# Sheet1.net
KiCad netlist of a schematic drawn in Altium Designer
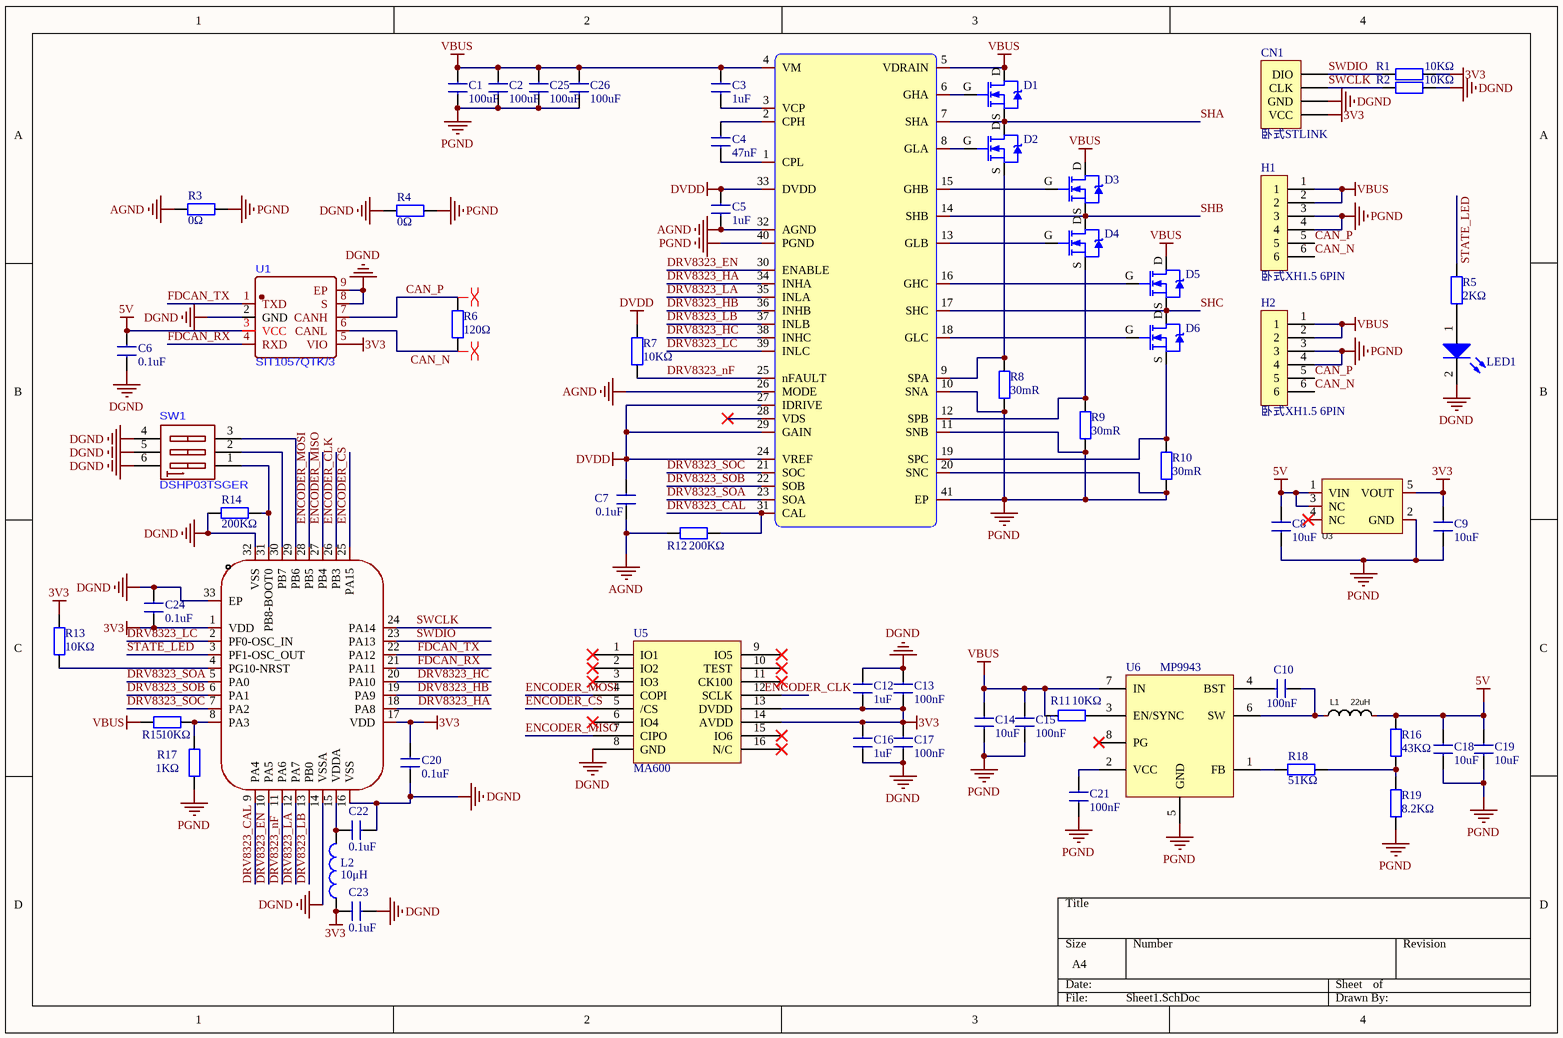
[diagram p0: Sheet1.SchDoc]

(export (version "E")
  (design (tool "Eeschema 10.0.6"))
  (components
    (comp (ref "C1")
      (value "100uF")
      (footprint "1206")
      (description "1210贴片电容")
      (libsource (lib "Integrated_Library1") (part "1210贴片电容"))
    )
    (comp (ref "C2")
      (value "100uF")
      (footprint "1206")
      (description "1210贴片电容")
      (libsource (lib "Integrated_Library1") (part "1210贴片电容"))
    )
    (comp (ref "C3")
      (value "1uF")
      (footprint "c0402")
      (description "贴片电容0402")
      (libsource (lib "Integrated_Library1") (part "0402贴片电容"))
    )
    (comp (ref "C4")
      (value "47nF")
      (footprint "c0402")
      (description "贴片电容0402")
      (libsource (lib "Integrated_Library1") (part "0402贴片电容"))
    )
    (comp (ref "C5")
      (value "1uF")
      (footprint "c0402")
      (description "贴片电容0402")
      (libsource (lib "Integrated_Library1") (part "0402贴片电容"))
    )
    (comp (ref "C6")
      (value "0.1uF")
      (footprint "c0402")
      (description "贴片电容0402")
      (libsource (lib "Integrated_Library1") (part "0402贴片电容"))
    )
    (comp (ref "C7")
      (value "0.1uF")
      (footprint "c0402")
      (description "贴片电容0402")
      (libsource (lib "Integrated_Library1") (part "0402贴片电容"))
    )
    (comp (ref "C8")
      (value "10uF")
      (footprint "c0402")
      (description "贴片电容0402")
      (libsource (lib "Integrated_Library1") (part "0402贴片电容"))
    )
    (comp (ref "C9")
      (value "10uF")
      (footprint "c0402")
      (description "贴片电容0402")
      (libsource (lib "Integrated_Library1") (part "0402贴片电容"))
    )
    (comp (ref "C10")
      (value "100nF")
      (footprint "c0402")
      (description "贴片电容0402")
      (libsource (lib "Integrated_Library1") (part "0402贴片电容"))
    )
    (comp (ref "C12")
      (value "1uF")
      (footprint "C0402")
      (description "贴片电容0402")
      (libsource (lib "Integrated_Library1") (part "0402贴片电容"))
    )
    (comp (ref "C13")
      (value "100nF")
      (footprint "C0402")
      (description "贴片电容0402")
      (libsource (lib "Integrated_Library1") (part "0402贴片电容"))
    )
    (comp (ref "C14")
      (value "10uF")
      (footprint "C0603")
      (description "1210贴片电容")
      (libsource (lib "Integrated_Library1") (part "1210贴片电容"))
    )
    (comp (ref "C15")
      (value "100nF")
      (footprint "c0402")
      (description "贴片电容0402")
      (libsource (lib "Integrated_Library1") (part "0402贴片电容"))
    )
    (comp (ref "C16")
      (value "1uF")
      (footprint "C0402")
      (description "贴片电容0402")
      (libsource (lib "Integrated_Library1") (part "0402贴片电容"))
    )
    (comp (ref "C17")
      (value "100nF")
      (footprint "C0402")
      (description "贴片电容0402")
      (libsource (lib "Integrated_Library1") (part "0402贴片电容"))
    )
    (comp (ref "C18")
      (value "10uF")
      (footprint "C0603")
      (description "1210贴片电容")
      (libsource (lib "Integrated_Library1") (part "1210贴片电容"))
    )
    (comp (ref "C19")
      (value "10uF")
      (footprint "C0603")
      (description "1210贴片电容")
      (libsource (lib "Integrated_Library1") (part "1210贴片电容"))
    )
    (comp (ref "C20")
      (value "0.1uF")
      (footprint "c0402")
      (description "贴片电容0402")
      (libsource (lib "Integrated_Library1") (part "0402贴片电容"))
    )
    (comp (ref "C21")
      (value "100nF")
      (footprint "c0402")
      (description "贴片电容0402")
      (libsource (lib "Integrated_Library1") (part "0402贴片电容"))
    )
    (comp (ref "C22")
      (value "0.1uF")
      (footprint "c0402")
      (description "贴片电容0402")
      (libsource (lib "Integrated_Library1") (part "0402贴片电容"))
    )
    (comp (ref "C23")
      (value "0.1uF")
      (footprint "c0402")
      (description "贴片电容0402")
      (libsource (lib "Integrated_Library1") (part "0402贴片电容"))
    )
    (comp (ref "C24")
      (value "0.1uF")
      (footprint "c0402")
      (description "贴片电容0402")
      (libsource (lib "Integrated_Library1") (part "0402贴片电容"))
    )
    (comp (ref "C25")
      (value "100uF")
      (footprint "1206")
      (description "1210贴片电容")
      (libsource (lib "Integrated_Library1") (part "1210贴片电容"))
    )
    (comp (ref "C26")
      (value "100uF")
      (footprint "1206")
      (description "1210贴片电容")
      (libsource (lib "Integrated_Library1") (part "1210贴片电容"))
    )
    (comp (ref "CN1")
      (value "卧式STLINK")
      (footprint "CONN-SMD_4P-P1.25_GH1.25-4P")
      (libsource (lib "Integrated_Library1") (part "卧式STLINK"))
    )
    (comp (ref "D1")
      (value "NTMFS5C410NL")
      (footprint "DFN-8_L3.0-W3.0-P0.65-BL")
      (description "N沟道MOS管")
      (fields (field (name "PUBLISHER") "Altium Limited"))
      (libsource (lib "En") (part "NTMFS5C410NL"))
    )
    (comp (ref "D2")
      (value "NTMFS5C410NL")
      (footprint "DFN-8_L3.0-W3.0-P0.65-BL")
      (description "N沟道MOS管")
      (fields (field (name "PUBLISHER") "Altium Limited"))
      (libsource (lib "En") (part "NTMFS5C410NL"))
    )
    (comp (ref "D3")
      (value "NTMFS5C410NL")
      (footprint "DFN-8_L3.0-W3.0-P0.65-BL")
      (description "N沟道MOS管")
      (fields (field (name "PUBLISHER") "Altium Limited"))
      (libsource (lib "En") (part "NTMFS5C410NL"))
    )
    (comp (ref "D4")
      (value "NTMFS5C410NL")
      (footprint "DFN-8_L3.0-W3.0-P0.65-BL")
      (description "N沟道MOS管")
      (fields (field (name "PUBLISHER") "Altium Limited"))
      (libsource (lib "En") (part "NTMFS5C410NL"))
    )
    (comp (ref "D5")
      (value "NTMFS5C410NL")
      (footprint "DFN-8_L3.0-W3.0-P0.65-BL")
      (description "N沟道MOS管")
      (fields (field (name "PUBLISHER") "Altium Limited"))
      (libsource (lib "En") (part "NTMFS5C410NL"))
    )
    (comp (ref "D6")
      (value "NTMFS5C410NL")
      (footprint "DFN-8_L3.0-W3.0-P0.65-BL")
      (description "N沟道MOS管")
      (fields (field (name "PUBLISHER") "Altium Limited"))
      (libsource (lib "En") (part "NTMFS5C410NL"))
    )
    (comp (ref "H1")
      (value "卧式XH1.5 6PIN")
      (footprint "CONN-SMD_6P-P1.50_ZX-ZH1.5-6PWT")
      (libsource (lib "En") (part "卧式XH1.5 6PIN"))
    )
    (comp (ref "H2")
      (value "卧式XH1.5 6PIN")
      (footprint "CONN-SMD_6P-P1.50_ZX-ZH1.5-6PWT")
      (libsource (lib "En") (part "卧式XH1.5 6PIN"))
    )
    (comp (ref "L1")
      (value "22uH")
      (footprint "IND-SMD_L2.5-W2.0")
      (description "一体成型屏蔽电感，0530封装，额定电流3A")
      (fields (field (name "MANUFACTURER") "XR(祥如)") (field (name "MANUFACTURER PART") "XR0530-100M"))
      (libsource (lib "Integrated_Library1") (part "0530屏蔽电感"))
    )
    (comp (ref "L2")
      (value "10μH")
      (footprint "L0805")
      (description "0805贴片电感")
      (libsource (lib "Integrated_Library1") (part "0805贴片电感"))
    )
    (comp (ref "LED1")
      (value "LED")
      (footprint "led0805")
      (description "0805贴片LED")
      (libsource (lib "Integrated_Library1") (part "0805贴片LED"))
    )
    (comp (ref "R1")
      (value "10KΩ")
      (footprint "R0402")
      (description "0402贴片电阻")
      (libsource (lib "") (part "0402贴片电阻_3"))
    )
    (comp (ref "R2")
      (value "10KΩ")
      (footprint "R0402")
      (description "0402贴片电阻")
      (libsource (lib "") (part "0402贴片电阻_3"))
    )
    (comp (ref "R3")
      (value "0Ω")
      (footprint "R0402")
      (description "0402贴片电阻")
      (libsource (lib "") (part "0402贴片电阻_3"))
    )
    (comp (ref "R4")
      (value "0Ω")
      (footprint "R0402")
      (description "0402贴片电阻")
      (libsource (lib "") (part "0402贴片电阻_3"))
    )
    (comp (ref "R5")
      (value "2KΩ")
      (footprint "R0402")
      (description "0402贴片电阻")
      (libsource (lib "") (part "0402贴片电阻_1"))
    )
    (comp (ref "R6")
      (value "120Ω")
      (footprint "R0402")
      (description "0402贴片电阻")
      (libsource (lib "") (part "0402贴片电阻_2"))
    )
    (comp (ref "R7")
      (value "10KΩ")
      (footprint "R0402")
      (description "0402贴片电阻")
      (libsource (lib "") (part "0402贴片电阻_1"))
    )
    (comp (ref "R8")
      (value "30mR")
      (footprint "1206")
      (description "2512检流电阻")
      (libsource (lib "Integrated_Library1") (part "2512检流电阻"))
    )
    (comp (ref "R9")
      (value "30mR")
      (footprint "1206")
      (description "2512检流电阻")
      (libsource (lib "Integrated_Library1") (part "2512检流电阻"))
    )
    (comp (ref "R10")
      (value "30mR")
      (footprint "1206")
      (description "2512检流电阻")
      (libsource (lib "Integrated_Library1") (part "2512检流电阻"))
    )
    (comp (ref "R11")
      (value "10KΩ")
      (footprint "R0402")
      (description "0402贴片电阻")
      (libsource (lib "") (part "0402贴片电阻_5"))
    )
    (comp (ref "R12")
      (value "200KΩ")
      (footprint "R0402")
      (description "0402贴片电阻")
      (libsource (lib "Integrated_Library1") (part "0402贴片电阻"))
    )
    (comp (ref "R13")
      (value "10KΩ")
      (footprint "R0402")
      (description "0402贴片电阻")
      (libsource (lib "") (part "0402贴片电阻_1"))
    )
    (comp (ref "R14")
      (value "200KΩ")
      (footprint "R0402")
      (description "0402贴片电阻")
      (libsource (lib "") (part "0402贴片电阻_3"))
    )
    (comp (ref "R15")
      (value "10KΩ")
      (footprint "R0402")
      (description "0402贴片电阻")
      (libsource (lib "Integrated_Library1") (part "0402贴片电阻"))
    )
    (comp (ref "R16")
      (value "43KΩ")
      (footprint "R0402")
      (description "0402贴片电阻")
      (libsource (lib "") (part "0402贴片电阻_4"))
    )
    (comp (ref "R17")
      (value "1KΩ")
      (footprint "R0402")
      (description "0402贴片电阻")
      (libsource (lib "") (part "0402贴片电阻_1"))
    )
    (comp (ref "R18")
      (value "51KΩ")
      (footprint "R0402")
      (description "0402贴片电阻")
      (libsource (lib "") (part "0402贴片电阻_5"))
    )
    (comp (ref "R19")
      (value "8.2KΩ")
      (footprint "R0402")
      (description "0402贴片电阻")
      (libsource (lib "") (part "0402贴片电阻_4"))
    )
    (comp (ref "SW1")
      (value "DSHP03TSGER")
      (footprint "SW-SMD_6P-L5.4-W5.4-P1.27-LS8.4")
      (libsource (lib "Integrated_Library1") (part "DSHP03TSGER"))
    )
    (comp (ref "U1")
      (value "SIT1057QTK/3")
      (footprint "DFN-8_L3.0-W3.0-P0.65-BL-EP")
      (libsource (lib "En") (part "SIT1057QTK/3"))
    )
    (comp (ref "U2")
      (value "DRV8323HRTAR")
      (footprint "QFN-40_L6.0-W6.0-P0.50-BL-EP4.5")
      (fields (field (name "MANUFACTURER") "TI(德州仪器)"))
      (libsource (lib "Integrated_Library1") (part "DRV8323HRTAR"))
    )
    (comp (ref "U3")
      (value "XC6201P332MR-HXY")
      (footprint "SOT-23-5_L3.0-W1.7-P0.95-LS2.8-BR")
      (description "3.3V LDO")
      (fields (field (name "MANUFACTURER") "HXY MOSFET(华轩阳电子)"))
      (libsource (lib "Integrated_Library1") (part "XC6201P332MR-HXY"))
    )
    (comp (ref "U4")
      (value "STM32G431KBU3")
      (footprint "UFQFPN-32_L5.0-W5.0-P0.50-BL-EP3.5")
      (fields (field (name "MANUFACTURER") "ST(意法半导体)"))
      (libsource (lib "Integrated_Library1") (part "STM32G431KBU3"))
    )
    (comp (ref "U5")
      (value "MA600")
      (footprint "qfn-16-l3.0-w3.0-p0.50-tl-ep1.7")
      (description "磁编码器")
      (libsource (lib "Integrated_Library1") (part "MA600"))
    )
    (comp (ref "U6")
      (value "MP9943")
      (footprint "QFN-8 3x3")
      (libsource (lib "Integrated_Library1") (part "MP9943"))
    )
  )
  (nets
    (net (code "2") (name "/CAN_N") (class "Default")
      (node (ref "H1") (pin "6") (pinfunction "6_6") (pintype "passive"))
      (node (ref "H2") (pin "6") (pinfunction "6_6") (pintype "passive"))
      (node (ref "R6") (pin "1") (pinfunction "1_1") (pintype "passive"))
      (node (ref "U1") (pin "6") (pinfunction "CANL_6") (pintype "passive"))
    )
    (net (code "3") (name "/CAN_P") (class "Default")
      (node (ref "H1") (pin "5") (pinfunction "5_5") (pintype "passive"))
      (node (ref "H2") (pin "5") (pinfunction "5_5") (pintype "passive"))
      (node (ref "R6") (pin "2") (pinfunction "2_2") (pintype "passive"))
      (node (ref "U1") (pin "7") (pinfunction "CANH_7") (pintype "passive"))
    )
    (net (code "4") (name "/DRV8323_CAL") (class "Default")
      (node (ref "R12") (pin "1") (pinfunction "1_1") (pintype "passive"))
      (node (ref "U2") (pin "31") (pinfunction "CAL_31") (pintype "passive"))
      (node (ref "U4") (pin "9") (pinfunction "PA4_9") (pintype "passive"))
    )
    (net (code "5") (name "/DRV8323_EN") (class "Default")
      (node (ref "U2") (pin "30") (pinfunction "ENABLE_30") (pintype "passive"))
      (node (ref "U4") (pin "10") (pinfunction "PA5_10") (pintype "passive"))
    )
    (net (code "6") (name "/DRV8323_HA") (class "Default")
      (node (ref "U2") (pin "34") (pinfunction "INHA_34") (pintype "passive"))
      (node (ref "U4") (pin "18") (pinfunction "PA8_18") (pintype "passive"))
    )
    (net (code "7") (name "/DRV8323_HB") (class "Default")
      (node (ref "U2") (pin "36") (pinfunction "INHB_36") (pintype "passive"))
      (node (ref "U4") (pin "19") (pinfunction "PA9_19") (pintype "passive"))
    )
    (net (code "8") (name "/DRV8323_HC") (class "Default")
      (node (ref "U2") (pin "38") (pinfunction "INHC_38") (pintype "passive"))
      (node (ref "U4") (pin "20") (pinfunction "PA10_20") (pintype "passive"))
    )
    (net (code "9") (name "/DRV8323_LA") (class "Default")
      (node (ref "U2") (pin "35") (pinfunction "INLA_35") (pintype "passive"))
      (node (ref "U4") (pin "12") (pinfunction "PA7_12") (pintype "passive"))
    )
    (net (code "10") (name "/DRV8323_LB") (class "Default")
      (node (ref "U2") (pin "37") (pinfunction "INLB_37") (pintype "passive"))
      (node (ref "U4") (pin "13") (pinfunction "PB0_13") (pintype "passive"))
    )
    (net (code "11") (name "/DRV8323_LC") (class "Default")
      (node (ref "U2") (pin "39") (pinfunction "INLC_39") (pintype "passive"))
      (node (ref "U4") (pin "2") (pinfunction "PF0-OSC_IN_2") (pintype "passive"))
    )
    (net (code "12") (name "/DRV8323_SOA") (class "Default")
      (node (ref "U2") (pin "23") (pinfunction "SOA_23") (pintype "passive"))
      (node (ref "U4") (pin "5") (pinfunction "PA0_5") (pintype "passive"))
    )
    (net (code "13") (name "/DRV8323_SOB") (class "Default")
      (node (ref "U2") (pin "22") (pinfunction "SOB_22") (pintype "passive"))
      (node (ref "U4") (pin "6") (pinfunction "PA1_6") (pintype "passive"))
    )
    (net (code "14") (name "/DRV8323_SOC") (class "Default")
      (node (ref "U2") (pin "21") (pinfunction "SOC_21") (pintype "passive"))
      (node (ref "U4") (pin "7") (pinfunction "PA2_7") (pintype "passive"))
    )
    (net (code "15") (name "/DRV8323_nF") (class "Default")
      (node (ref "R7") (pin "2") (pinfunction "2_2") (pintype "passive"))
      (node (ref "U2") (pin "25") (pinfunction "nFAULT_25") (pintype "passive"))
      (node (ref "U4") (pin "11") (pinfunction "PA6_11") (pintype "passive"))
    )
    (net (code "16") (name "/ENCODER_CLK") (class "Default")
      (node (ref "U4") (pin "26") (pinfunction "PB3_26") (pintype "passive"))
      (node (ref "U5") (pin "12") (pinfunction "SCLK_12") (pintype "passive"))
    )
    (net (code "17") (name "/ENCODER_CS") (class "Default")
      (node (ref "U4") (pin "25") (pinfunction "PA15_25") (pintype "passive"))
      (node (ref "U5") (pin "5") (pinfunction "/CS_5") (pintype "passive"))
    )
    (net (code "18") (name "/ENCODER_MISO") (class "Default")
      (node (ref "U4") (pin "27") (pinfunction "PB4_27") (pintype "passive"))
      (node (ref "U5") (pin "7") (pinfunction "CIPO_7") (pintype "passive"))
    )
    (net (code "19") (name "/ENCODER_MOSI") (class "Default")
      (node (ref "U4") (pin "28") (pinfunction "PB5_28") (pintype "passive"))
      (node (ref "U5") (pin "4") (pinfunction "COPI_4") (pintype "passive"))
    )
    (net (code "20") (name "/FDCAN_RX") (class "Default")
      (node (ref "U1") (pin "4") (pinfunction "RXD_4") (pintype "passive"))
      (node (ref "U4") (pin "21") (pinfunction "PA11_21") (pintype "passive"))
    )
    (net (code "21") (name "/FDCAN_TX") (class "Default")
      (node (ref "U1") (pin "1") (pinfunction "TXD_1") (pintype "passive"))
      (node (ref "U4") (pin "22") (pinfunction "PA12_22") (pintype "passive"))
    )
    (net (code "22") (name "/SHA") (class "Default")
      (node (ref "D1") (pin "S") (pinfunction "S_S") (pintype "passive"))
      (node (ref "D2") (pin "D") (pinfunction "D_D") (pintype "passive"))
      (node (ref "U2") (pin "7") (pinfunction "SHA_7") (pintype "passive"))
    )
    (net (code "23") (name "/SHB") (class "Default")
      (node (ref "D3") (pin "S") (pinfunction "S_S") (pintype "passive"))
      (node (ref "D4") (pin "D") (pinfunction "D_D") (pintype "passive"))
      (node (ref "U2") (pin "14") (pinfunction "SHB_14") (pintype "passive"))
    )
    (net (code "24") (name "/SHC") (class "Default")
      (node (ref "D5") (pin "S") (pinfunction "S_S") (pintype "passive"))
      (node (ref "D6") (pin "D") (pinfunction "D_D") (pintype "passive"))
      (node (ref "U2") (pin "17") (pinfunction "SHC_17") (pintype "passive"))
    )
    (net (code "25") (name "/STATE_LED") (class "Default")
      (node (ref "R5") (pin "1") (pinfunction "1_1") (pintype "passive"))
      (node (ref "U4") (pin "3") (pinfunction "PF1-OSC_OUT_3") (pintype "passive"))
    )
    (net (code "26") (name "/SWCLK") (class "Default")
      (node (ref "CN1") (pin "3") (pinfunction "CLK_3") (pintype "passive"))
      (node (ref "R2") (pin "1") (pinfunction "1_1") (pintype "passive"))
      (node (ref "U4") (pin "24") (pinfunction "PA14_24") (pintype "passive"))
    )
    (net (code "27") (name "/SWDIO") (class "Default")
      (node (ref "CN1") (pin "4") (pinfunction "DIO_4") (pintype "passive"))
      (node (ref "R1") (pin "1") (pinfunction "1_1") (pintype "passive"))
      (node (ref "U4") (pin "23") (pinfunction "PA13_23") (pintype "passive"))
    )
    (net (code "28") (name "3V3") (class "Default")
      (node (ref "C12") (pin "1") (pinfunction "1_1") (pintype "passive"))
      (node (ref "C13") (pin "1") (pinfunction "1_1") (pintype "passive"))
      (node (ref "C16") (pin "2") (pinfunction "2_2") (pintype "passive"))
      (node (ref "C17") (pin "2") (pinfunction "2_2") (pintype "passive"))
      (node (ref "C20") (pin "1") (pinfunction "1_1") (pintype "passive"))
      (node (ref "C23") (pin "2") (pinfunction "2_2") (pintype "passive"))
      (node (ref "C24") (pin "1") (pinfunction "1_1") (pintype "passive"))
      (node (ref "C9") (pin "2") (pinfunction "2_2") (pintype "passive"))
      (node (ref "CN1") (pin "1") (pinfunction "VCC_1") (pintype "passive"))
      (node (ref "L2") (pin "1") (pinfunction "1_1") (pintype "passive"))
      (node (ref "R1") (pin "2") (pinfunction "2_2") (pintype "passive"))
      (node (ref "R13") (pin "1") (pinfunction "1_1") (pintype "passive"))
      (node (ref "U1") (pin "5") (pinfunction "VIO_5") (pintype "passive"))
      (node (ref "U3") (pin "5") (pinfunction "VOUT_5") (pintype "passive"))
      (node (ref "U4") (pin "1") (pinfunction "VDD_1") (pintype "passive"))
      (node (ref "U4") (pin "17") (pinfunction "VDD_17") (pintype "passive"))
      (node (ref "U5") (pin "13") (pinfunction "DVDD_13") (pintype "passive"))
      (node (ref "U5") (pin "14") (pinfunction "AVDD_14") (pintype "passive"))
    )
    (net (code "29") (name "5V") (class "Default")
      (node (ref "C18") (pin "2") (pinfunction "2_2") (pintype "passive"))
      (node (ref "C19") (pin "2") (pinfunction "2_2") (pintype "passive"))
      (node (ref "C6") (pin "2") (pinfunction "2_2") (pintype "passive"))
      (node (ref "C8") (pin "2") (pinfunction "2_2") (pintype "passive"))
      (node (ref "L1") (pin "2") (pinfunction "2_2") (pintype "passive"))
      (node (ref "R16") (pin "2") (pinfunction "2_2") (pintype "passive"))
      (node (ref "U1") (pin "3") (pinfunction "VCC_3") (pintype "passive"))
      (node (ref "U3") (pin "1") (pinfunction "VIN_1") (pintype "passive"))
      (node (ref "U3") (pin "3") (pinfunction "NC_3") (pintype "passive"))
    )
    (net (code "30") (name "AGND") (class "Default")
      (node (ref "C5") (pin "1") (pinfunction "1_1") (pintype "passive"))
      (node (ref "C7") (pin "1") (pinfunction "1_1") (pintype "passive"))
      (node (ref "R12") (pin "2") (pinfunction "2_2") (pintype "passive"))
      (node (ref "R3") (pin "1") (pinfunction "1_1") (pintype "passive"))
      (node (ref "U2") (pin "26") (pinfunction "MODE_26") (pintype "passive"))
      (node (ref "U2") (pin "32") (pinfunction "AGND_32") (pintype "passive"))
    )
    (net (code "31") (name "DGND") (class "Default")
      (node (ref "C12") (pin "2") (pinfunction "2_2") (pintype "passive"))
      (node (ref "C13") (pin "2") (pinfunction "2_2") (pintype "passive"))
      (node (ref "C16") (pin "1") (pinfunction "1_1") (pintype "passive"))
      (node (ref "C17") (pin "1") (pinfunction "1_1") (pintype "passive"))
      (node (ref "C20") (pin "2") (pinfunction "2_2") (pintype "passive"))
      (node (ref "C22") (pin "1") (pinfunction "1_1") (pintype "passive"))
      (node (ref "C23") (pin "1") (pinfunction "1_1") (pintype "passive"))
      (node (ref "C24") (pin "2") (pinfunction "2_2") (pintype "passive"))
      (node (ref "C6") (pin "1") (pinfunction "1_1") (pintype "passive"))
      (node (ref "CN1") (pin "2") (pinfunction "GND_2") (pintype "passive"))
      (node (ref "LED1") (pin "2") (pinfunction "K_2") (pintype "passive"))
      (node (ref "R14") (pin "1") (pinfunction "1_1") (pintype "passive"))
      (node (ref "R2") (pin "2") (pinfunction "2_2") (pintype "passive"))
      (node (ref "R4") (pin "1") (pinfunction "1_1") (pintype "passive"))
      (node (ref "SW1") (pin "4") (pinfunction "B3_4") (pintype "passive"))
      (node (ref "SW1") (pin "5") (pinfunction "B2_5") (pintype "passive"))
      (node (ref "SW1") (pin "6") (pinfunction "B1_6") (pintype "passive"))
      (node (ref "U1") (pin "2") (pinfunction "GND_2") (pintype "passive"))
      (node (ref "U1") (pin "8") (pinfunction "S_8") (pintype "passive"))
      (node (ref "U1") (pin "9") (pinfunction "EP_9") (pintype "passive"))
      (node (ref "U4") (pin "14") (pinfunction "VSSA_14") (pintype "passive"))
      (node (ref "U4") (pin "16") (pinfunction "VSS_16") (pintype "passive"))
      (node (ref "U4") (pin "32") (pinfunction "VSS_32") (pintype "passive"))
      (node (ref "U4") (pin "33") (pinfunction "EP_33") (pintype "passive"))
      (node (ref "U5") (pin "8") (pinfunction "GND_8") (pintype "passive"))
    )
    (net (code "32") (name "DVDD") (class "Default")
      (node (ref "C5") (pin "2") (pinfunction "2_2") (pintype "passive"))
      (node (ref "C7") (pin "2") (pinfunction "2_2") (pintype "passive"))
      (node (ref "R7") (pin "1") (pinfunction "1_1") (pintype "passive"))
      (node (ref "U2") (pin "24") (pinfunction "VREF_24") (pintype "passive"))
      (node (ref "U2") (pin "27") (pinfunction "IDRIVE_27") (pintype "passive"))
      (node (ref "U2") (pin "29") (pinfunction "GAIN_29") (pintype "passive"))
      (node (ref "U2") (pin "33") (pinfunction "DVDD_33") (pintype "passive"))
    )
    (net (code "33") (name "Net-(LED1-A)") (class "Default")
      (node (ref "LED1") (pin "1") (pinfunction "A_1") (pintype "passive"))
      (node (ref "R5") (pin "2") (pinfunction "2_2") (pintype "passive"))
    )
    (net (code "34") (name "Net-(R16-Pad1)") (class "Default")
      (node (ref "R16") (pin "1") (pinfunction "1_1") (pintype "passive"))
      (node (ref "R18") (pin "2") (pinfunction "2_2") (pintype "passive"))
      (node (ref "R19") (pin "2") (pinfunction "2_2") (pintype "passive"))
    )
    (net (code "35") (name "Net-(SW1-A1)") (class "Default")
      (node (ref "R14") (pin "2") (pinfunction "2_2") (pintype "passive"))
      (node (ref "SW1") (pin "1") (pinfunction "A1_1") (pintype "passive"))
      (node (ref "U4") (pin "31") (pinfunction "PB8-BOOT0_31") (pintype "passive"))
    )
    (net (code "36") (name "Net-(SW1-A2)") (class "Default")
      (node (ref "SW1") (pin "2") (pinfunction "A2_2") (pintype "passive"))
      (node (ref "U4") (pin "30") (pinfunction "PB7_30") (pintype "passive"))
    )
    (net (code "37") (name "Net-(SW1-A3)") (class "Default")
      (node (ref "SW1") (pin "3") (pinfunction "A3_3") (pintype "passive"))
      (node (ref "U4") (pin "29") (pinfunction "PB6_29") (pintype "passive"))
    )
    (net (code "38") (name "Net-(U2-CPH)") (class "Default")
      (node (ref "C4") (pin "2") (pinfunction "2_2") (pintype "passive"))
      (node (ref "U2") (pin "2") (pinfunction "CPH_2") (pintype "passive"))
    )
    (net (code "39") (name "Net-(U2-CPL)") (class "Default")
      (node (ref "C4") (pin "1") (pinfunction "1_1") (pintype "passive"))
      (node (ref "U2") (pin "1") (pinfunction "CPL_1") (pintype "passive"))
    )
    (net (code "40") (name "Net-(U2-GHA)") (class "Default")
      (node (ref "D1") (pin "G") (pinfunction "G_G") (pintype "passive"))
      (node (ref "U2") (pin "6") (pinfunction "GHA_6") (pintype "passive"))
    )
    (net (code "41") (name "Net-(U2-GHB)") (class "Default")
      (node (ref "D3") (pin "G") (pinfunction "G_G") (pintype "passive"))
      (node (ref "U2") (pin "15") (pinfunction "GHB_15") (pintype "passive"))
    )
    (net (code "42") (name "Net-(U2-GHC)") (class "Default")
      (node (ref "D5") (pin "G") (pinfunction "G_G") (pintype "passive"))
      (node (ref "U2") (pin "16") (pinfunction "GHC_16") (pintype "passive"))
    )
    (net (code "43") (name "Net-(U2-GLA)") (class "Default")
      (node (ref "D2") (pin "G") (pinfunction "G_G") (pintype "passive"))
      (node (ref "U2") (pin "8") (pinfunction "GLA_8") (pintype "passive"))
    )
    (net (code "44") (name "Net-(U2-GLB)") (class "Default")
      (node (ref "D4") (pin "G") (pinfunction "G_G") (pintype "passive"))
      (node (ref "U2") (pin "13") (pinfunction "GLB_13") (pintype "passive"))
    )
    (net (code "45") (name "Net-(U2-GLC)") (class "Default")
      (node (ref "D6") (pin "G") (pinfunction "G_G") (pintype "passive"))
      (node (ref "U2") (pin "18") (pinfunction "GLC_18") (pintype "passive"))
    )
    (net (code "46") (name "Net-(U2-SPA)") (class "Default")
      (node (ref "D2") (pin "S") (pinfunction "S_S") (pintype "passive"))
      (node (ref "R8") (pin "2") (pinfunction "2_2") (pintype "passive"))
      (node (ref "U2") (pin "9") (pinfunction "SPA_9") (pintype "passive"))
    )
    (net (code "47") (name "Net-(U2-SPB)") (class "Default")
      (node (ref "D4") (pin "S") (pinfunction "S_S") (pintype "passive"))
      (node (ref "R9") (pin "2") (pinfunction "2_2") (pintype "passive"))
      (node (ref "U2") (pin "12") (pinfunction "SPB_12") (pintype "passive"))
    )
    (net (code "48") (name "Net-(U2-SPC)") (class "Default")
      (node (ref "D6") (pin "S") (pinfunction "S_S") (pintype "passive"))
      (node (ref "R10") (pin "2") (pinfunction "2_2") (pintype "passive"))
      (node (ref "U2") (pin "19") (pinfunction "SPC_19") (pintype "passive"))
    )
    (net (code "49") (name "Net-(U2-VCP)") (class "Default")
      (node (ref "C3") (pin "1") (pinfunction "1_1") (pintype "passive"))
      (node (ref "U2") (pin "3") (pinfunction "VCP_3") (pintype "passive"))
    )
    (net (code "50") (name "Net-(U4-PA3)") (class "Default")
      (node (ref "R15") (pin "1") (pinfunction "1_1") (pintype "passive"))
      (node (ref "R17") (pin "1") (pinfunction "1_1") (pintype "passive"))
      (node (ref "U4") (pin "8") (pinfunction "PA3_8") (pintype "passive"))
    )
    (net (code "51") (name "Net-(U4-PG10-NRST)") (class "Default")
      (node (ref "R13") (pin "2") (pinfunction "2_2") (pintype "passive"))
      (node (ref "U4") (pin "4") (pinfunction "PG10-NRST_4") (pintype "passive"))
    )
    (net (code "52") (name "Net-(U4-VDDA)") (class "Default")
      (node (ref "C22") (pin "2") (pinfunction "2_2") (pintype "passive"))
      (node (ref "L2") (pin "2") (pinfunction "2_2") (pintype "passive"))
      (node (ref "U4") (pin "15") (pinfunction "VDDA_15") (pintype "passive"))
    )
    (net (code "53") (name "Net-(U6-BST)") (class "Default")
      (node (ref "C10") (pin "1") (pinfunction "1_1") (pintype "passive"))
      (node (ref "U6") (pin "4") (pinfunction "BST_4") (pintype "passive"))
    )
    (net (code "54") (name "Net-(U6-EN{slash}SYNC)") (class "Default")
      (node (ref "R11") (pin "2") (pinfunction "2_2") (pintype "passive"))
      (node (ref "U6") (pin "3") (pinfunction "EN/SYNC_3") (pintype "passive"))
    )
    (net (code "55") (name "Net-(U6-FB)") (class "Default")
      (node (ref "R18") (pin "1") (pinfunction "1_1") (pintype "passive"))
      (node (ref "U6") (pin "1") (pinfunction "FB_1") (pintype "passive"))
    )
    (net (code "56") (name "Net-(U6-SW)") (class "Default")
      (node (ref "C10") (pin "2") (pinfunction "2_2") (pintype "passive"))
      (node (ref "L1") (pin "1") (pinfunction "1_1") (pintype "passive"))
      (node (ref "U6") (pin "6") (pinfunction "SW_6") (pintype "passive"))
    )
    (net (code "57") (name "Net-(U6-VCC)") (class "Default")
      (node (ref "C21") (pin "2") (pinfunction "2_2") (pintype "passive"))
      (node (ref "U6") (pin "2") (pinfunction "VCC_2") (pintype "passive"))
    )
    (net (code "58") (name "PGND") (class "Default")
      (node (ref "C1") (pin "1") (pinfunction "1_1") (pintype "passive"))
      (node (ref "C14") (pin "1") (pinfunction "1_1") (pintype "passive"))
      (node (ref "C15") (pin "1") (pinfunction "1_1") (pintype "passive"))
      (node (ref "C18") (pin "1") (pinfunction "1_1") (pintype "passive"))
      (node (ref "C19") (pin "1") (pinfunction "1_1") (pintype "passive"))
      (node (ref "C2") (pin "1") (pinfunction "1_1") (pintype "passive"))
      (node (ref "C21") (pin "1") (pinfunction "1_1") (pintype "passive"))
      (node (ref "C25") (pin "1") (pinfunction "1_1") (pintype "passive"))
      (node (ref "C26") (pin "1") (pinfunction "1_1") (pintype "passive"))
      (node (ref "C8") (pin "1") (pinfunction "1_1") (pintype "passive"))
      (node (ref "C9") (pin "1") (pinfunction "1_1") (pintype "passive"))
      (node (ref "H1") (pin "3") (pinfunction "3_3") (pintype "passive"))
      (node (ref "H1") (pin "4") (pinfunction "4_4") (pintype "passive"))
      (node (ref "H2") (pin "3") (pinfunction "3_3") (pintype "passive"))
      (node (ref "H2") (pin "4") (pinfunction "4_4") (pintype "passive"))
      (node (ref "R10") (pin "1") (pinfunction "1_1") (pintype "passive"))
      (node (ref "R17") (pin "2") (pinfunction "2_2") (pintype "passive"))
      (node (ref "R19") (pin "1") (pinfunction "1_1") (pintype "passive"))
      (node (ref "R3") (pin "2") (pinfunction "2_2") (pintype "passive"))
      (node (ref "R4") (pin "2") (pinfunction "2_2") (pintype "passive"))
      (node (ref "R8") (pin "1") (pinfunction "1_1") (pintype "passive"))
      (node (ref "R9") (pin "1") (pinfunction "1_1") (pintype "passive"))
      (node (ref "U2") (pin "10") (pinfunction "SNA_10") (pintype "passive"))
      (node (ref "U2") (pin "11") (pinfunction "SNB_11") (pintype "passive"))
      (node (ref "U2") (pin "20") (pinfunction "SNC_20") (pintype "passive"))
      (node (ref "U2") (pin "40") (pinfunction "PGND_40") (pintype "passive"))
      (node (ref "U2") (pin "41") (pinfunction "EP_41") (pintype "passive"))
      (node (ref "U3") (pin "2") (pinfunction "GND_2") (pintype "passive"))
      (node (ref "U6") (pin "5") (pinfunction "GND_5") (pintype "passive"))
    )
    (net (code "59") (name "VBUS") (class "Default")
      (node (ref "C1") (pin "2") (pinfunction "2_2") (pintype "passive"))
      (node (ref "C14") (pin "2") (pinfunction "2_2") (pintype "passive"))
      (node (ref "C15") (pin "2") (pinfunction "2_2") (pintype "passive"))
      (node (ref "C2") (pin "2") (pinfunction "2_2") (pintype "passive"))
      (node (ref "C25") (pin "2") (pinfunction "2_2") (pintype "passive"))
      (node (ref "C26") (pin "2") (pinfunction "2_2") (pintype "passive"))
      (node (ref "C3") (pin "2") (pinfunction "2_2") (pintype "passive"))
      (node (ref "D1") (pin "D") (pinfunction "D_D") (pintype "passive"))
      (node (ref "D3") (pin "D") (pinfunction "D_D") (pintype "passive"))
      (node (ref "D5") (pin "D") (pinfunction "D_D") (pintype "passive"))
      (node (ref "H1") (pin "1") (pinfunction "1_1") (pintype "passive"))
      (node (ref "H1") (pin "2") (pinfunction "2_2") (pintype "passive"))
      (node (ref "H2") (pin "1") (pinfunction "1_1") (pintype "passive"))
      (node (ref "H2") (pin "2") (pinfunction "2_2") (pintype "passive"))
      (node (ref "R11") (pin "1") (pinfunction "1_1") (pintype "passive"))
      (node (ref "R15") (pin "2") (pinfunction "2_2") (pintype "passive"))
      (node (ref "U2") (pin "4") (pinfunction "VM_4") (pintype "passive"))
      (node (ref "U2") (pin "5") (pinfunction "VDRAIN_5") (pintype "passive"))
      (node (ref "U6") (pin "7") (pinfunction "IN_7") (pintype "passive"))
    )
    (net (code "60") (name "unconnected-(U2-VDS-Pad28)") (class "Default")
      (node (ref "U2") (pin "28") (pinfunction "VDS_28") (pintype "passive+no_connect"))
    )
    (net (code "61") (name "unconnected-(U3-NC-Pad4)") (class "Default")
      (node (ref "U3") (pin "4") (pinfunction "NC_4") (pintype "passive+no_connect"))
    )
    (net (code "62") (name "unconnected-(U5-CK100-Pad11)") (class "Default")
      (node (ref "U5") (pin "11") (pinfunction "CK100_11") (pintype "passive+no_connect"))
    )
    (net (code "63") (name "unconnected-(U5-IO1-Pad1)") (class "Default")
      (node (ref "U5") (pin "1") (pinfunction "IO1_1") (pintype "passive+no_connect"))
    )
    (net (code "64") (name "unconnected-(U5-IO2-Pad2)") (class "Default")
      (node (ref "U5") (pin "2") (pinfunction "IO2_2") (pintype "passive+no_connect"))
    )
    (net (code "65") (name "unconnected-(U5-IO3-Pad3)") (class "Default")
      (node (ref "U5") (pin "3") (pinfunction "IO3_3") (pintype "passive+no_connect"))
    )
    (net (code "66") (name "unconnected-(U5-IO4-Pad6)") (class "Default")
      (node (ref "U5") (pin "6") (pinfunction "IO4_6") (pintype "passive+no_connect"))
    )
    (net (code "67") (name "unconnected-(U5-IO5-Pad9)") (class "Default")
      (node (ref "U5") (pin "9") (pinfunction "IO5_9") (pintype "passive+no_connect"))
    )
    (net (code "68") (name "unconnected-(U5-IO6-Pad15)") (class "Default")
      (node (ref "U5") (pin "15") (pinfunction "IO6_15") (pintype "passive+no_connect"))
    )
    (net (code "69") (name "unconnected-(U5-N{slash}C-Pad16)") (class "Default")
      (node (ref "U5") (pin "16") (pinfunction "N/C_16") (pintype "passive+no_connect"))
    )
    (net (code "70") (name "unconnected-(U5-TEST-Pad10)") (class "Default")
      (node (ref "U5") (pin "10") (pinfunction "TEST_10") (pintype "passive+no_connect"))
    )
    (net (code "71") (name "unconnected-(U6-PG-Pad8)") (class "Default")
      (node (ref "U6") (pin "8") (pinfunction "PG_8") (pintype "passive+no_connect"))
    )
  )
)
